# LINK.net
KiCad netlist of a schematic drawn in Altium Designer
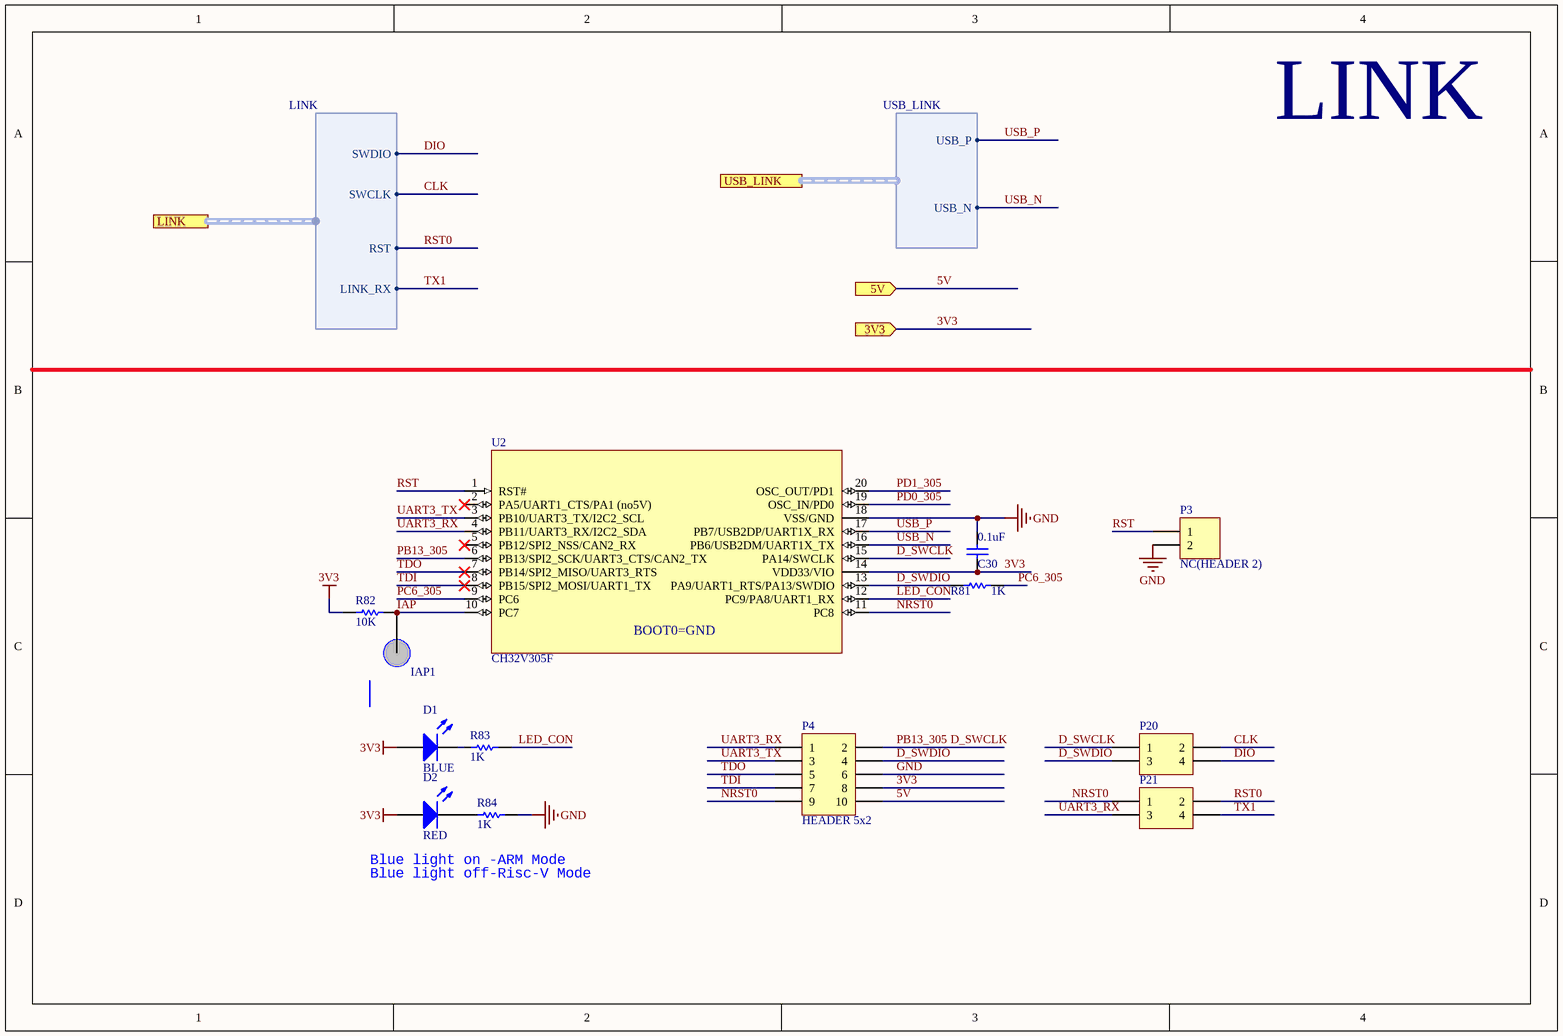
[diagram p0: LINK.SchDoc]

(export (version "E")
  (design (tool "Eeschema 10.0.6"))
  (components
    (comp (ref "C30")
      (value "0.1uF")
      (footprint "0402_C")
      (description "Capacitor")
      (libsource (lib "Miscellaneous Devices") (part "Cap"))
    )
    (comp (ref "D1")
      (value "BLUE")
      (footprint "0603+")
      (description "Typical RED, GREEN, YELLOW, AMBER GaAs LED")
      (fields (field (name "PUBLISHER") "Altium Limited"))
      (libsource (lib "MYLIB") (part "D0603"))
    )
    (comp (ref "D2")
      (value "RED")
      (footprint "0603+")
      (description "Typical RED, GREEN, YELLOW, AMBER GaAs LED")
      (fields (field (name "PUBLISHER") "Altium Limited"))
      (libsource (lib "MYLIB") (part "D0603"))
    )
    (comp (ref "IAP1")
      (value "Testpoint")
      (footprint "TESTPOINT1")
      (description "测试点")
      (libsource (lib "wch_sch_others") (part "Testpoint"))
    )
    (comp (ref "P3")
      (value "NC(HEADER 2)")
      (footprint "MYPCB:SIP2-2.54mm")
      (description "Header, 2-Pin")
      (libsource (lib "wch_sch_others") (part "HEADER 2"))
    )
    (comp (ref "P4")
      (value "HEADER 5x2")
      (footprint "MYPCB:IDC10-2.54mm")
      (description "Header, 5-Pin, Dual row")
      (libsource (lib "wch_sch_others") (part "HEADER 5x2"))
    )
    (comp (ref "P20")
      (value "HEADER 2x2")
      (footprint "MYPCB:IDC4-2.54MM")
      (description "Header, 2-Pin, Dual row")
      (libsource (lib "wch_sch_others") (part "HEADER 2x2"))
    )
    (comp (ref "P21")
      (value "HEADER 2x2")
      (footprint "MYPCB:IDC4-2.54MM")
      (description "Header, 2-Pin, Dual row")
      (libsource (lib "wch_sch_others") (part "HEADER 2x2"))
    )
    (comp (ref "R81")
      (value "1K")
      (footprint "0402")
      (description "Resistor")
      (fields (field (name "PUBLISHER") "Altium Limited"))
      (libsource (lib "MYLIB") (part "0603-1"))
    )
    (comp (ref "R82")
      (value "10K")
      (footprint "0402")
      (description "Resistor")
      (fields (field (name "PUBLISHER") "Altium Limited"))
      (libsource (lib "MYLIB") (part "0603-1"))
    )
    (comp (ref "R83")
      (value "1K")
      (footprint "0402")
      (description "Resistor")
      (fields (field (name "PUBLISHER") "Altium Limited"))
      (libsource (lib "MYLIB") (part "0603-1"))
    )
    (comp (ref "R84")
      (value "1K")
      (footprint "0402")
      (description "Resistor")
      (fields (field (name "PUBLISHER") "Altium Limited"))
      (libsource (lib "MYLIB") (part "0603-1"))
    )
    (comp (ref "U2")
      (value "CH32V305F")
      (footprint "TSSOP20")
      (description "RISC-V FPU HD-MCU, 144MHz, USB_480M, CAN, UART*2, SPI")
      (libsource (lib "CHXXX") (part "CH32V305F"))
    )
  )
  (nets
    (net (code "3") (name "/5V") (class "Default")
      (node (ref "P4") (pin "10") (pinfunction "10_10") (pintype "passive"))
    )
    (net (code "4") (name "/CLK") (class "Default")
      (node (ref "P20") (pin "2") (pinfunction "2_2") (pintype "passive"))
    )
    (net (code "5") (name "/DIO") (class "Default")
      (node (ref "P20") (pin "4") (pinfunction "4_4") (pintype "passive"))
    )
    (net (code "6") (name "/D_SWCLK") (class "Default")
      (node (ref "P20") (pin "1") (pinfunction "1_1") (pintype "passive"))
      (node (ref "P4") (pin "2") (pinfunction "2_2") (pintype "passive"))
      (node (ref "U2") (pin "15") (pinfunction "PA14/SWCLK_15") (pintype "bidirectional"))
      (node (ref "U2") (pin "6") (pinfunction "PB13/SPI2_SCK/UART3_CTS/CAN2_TX_6") (pintype "bidirectional"))
    )
    (net (code "7") (name "/D_SWDIO") (class "Default")
      (node (ref "P20") (pin "3") (pinfunction "3_3") (pintype "passive"))
      (node (ref "P4") (pin "4") (pinfunction "4_4") (pintype "passive"))
      (node (ref "R81") (pin "1") (pinfunction "1_1") (pintype "passive"))
      (node (ref "U2") (pin "13") (pinfunction "PA9/UART1_RTS/PA13/SWDIO_13") (pintype "bidirectional"))
    )
    (net (code "8") (name "/IAP") (class "Default")
      (node (ref "IAP1") (pin "1") (pinfunction "point_1") (pintype "passive"))
      (node (ref "R82") (pin "1") (pinfunction "1_1") (pintype "passive"))
      (node (ref "U2") (pin "10") (pinfunction "PC7_10") (pintype "bidirectional"))
    )
    (net (code "9") (name "/LED_CON") (class "Default")
      (node (ref "R83") (pin "1") (pinfunction "1_1") (pintype "passive"))
      (node (ref "U2") (pin "12") (pinfunction "PC9/PA8/UART1_RX_12") (pintype "bidirectional"))
    )
    (net (code "10") (name "/NRST0") (class "Default")
      (node (ref "P21") (pin "1") (pinfunction "1_1") (pintype "passive"))
      (node (ref "P4") (pin "9") (pinfunction "9_9") (pintype "passive"))
      (node (ref "U2") (pin "11") (pinfunction "PC8_11") (pintype "bidirectional"))
    )
    (net (code "11") (name "/PC6_305") (class "Default")
      (node (ref "R81") (pin "2") (pinfunction "2_2") (pintype "passive"))
      (node (ref "U2") (pin "9") (pinfunction "PC6_9") (pintype "bidirectional"))
    )
    (net (code "12") (name "/PD0_305") (class "Default")
      (node (ref "U2") (pin "19") (pinfunction "OSC_IN/PD0_19") (pintype "bidirectional"))
    )
    (net (code "13") (name "/PD1_305") (class "Default")
      (node (ref "U2") (pin "20") (pinfunction "OSC_OUT/PD1_20") (pintype "bidirectional"))
    )
    (net (code "14") (name "/RST") (class "Default")
      (node (ref "P3") (pin "1") (pinfunction "1_1") (pintype "passive"))
      (node (ref "U2") (pin "1") (pinfunction "RST#_1") (pintype "input"))
    )
    (net (code "15") (name "/RST0") (class "Default")
      (node (ref "P21") (pin "2") (pinfunction "2_2") (pintype "passive"))
    )
    (net (code "16") (name "/TDI") (class "Default")
      (node (ref "P4") (pin "7") (pinfunction "7_7") (pintype "passive"))
      (node (ref "U2") (pin "8") (pinfunction "PB15/SPI2_MOSI/UART1_TX_8") (pintype "bidirectional"))
    )
    (net (code "17") (name "/TDO") (class "Default")
      (node (ref "P4") (pin "5") (pinfunction "5_5") (pintype "passive"))
      (node (ref "U2") (pin "7") (pinfunction "PB14/SPI2_MISO/UART3_RTS_7") (pintype "bidirectional"))
    )
    (net (code "18") (name "/TX1") (class "Default")
      (node (ref "P21") (pin "4") (pinfunction "4_4") (pintype "passive"))
    )
    (net (code "19") (name "/UART3_RX") (class "Default")
      (node (ref "P21") (pin "3") (pinfunction "3_3") (pintype "passive"))
      (node (ref "P4") (pin "1") (pinfunction "1_1") (pintype "passive"))
      (node (ref "U2") (pin "4") (pinfunction "PB11/UART3_RX/I2C2_SDA_4") (pintype "bidirectional"))
    )
    (net (code "20") (name "/UART3_TX") (class "Default")
      (node (ref "P4") (pin "3") (pinfunction "3_3") (pintype "passive"))
      (node (ref "U2") (pin "3") (pinfunction "PB10/UART3_TX/I2C2_SCL_3") (pintype "bidirectional"))
    )
    (net (code "21") (name "/USB_N") (class "Default")
      (node (ref "U2") (pin "16") (pinfunction "PB6/USB2DM/UART1X_TX_16") (pintype "bidirectional"))
    )
    (net (code "22") (name "/USB_P") (class "Default")
      (node (ref "U2") (pin "17") (pinfunction "PB7/USB2DP/UART1X_RX_17") (pintype "bidirectional"))
    )
    (net (code "25") (name "3V3") (class "Default")
      (node (ref "C30") (pin "1") (pinfunction "1_1") (pintype "passive"))
      (node (ref "D1") (pin "1") (pinfunction "A_1") (pintype "passive"))
      (node (ref "D2") (pin "1") (pinfunction "A_1") (pintype "passive"))
      (node (ref "P4") (pin "8") (pinfunction "8_8") (pintype "passive"))
      (node (ref "R82") (pin "2") (pinfunction "2_2") (pintype "passive"))
      (node (ref "U2") (pin "14") (pinfunction "VDD33/VIO_14") (pintype "power_in"))
    )
    (net (code "26") (name "GND") (class "Default")
      (node (ref "C30") (pin "2") (pinfunction "2_2") (pintype "passive"))
      (node (ref "P3") (pin "2") (pinfunction "2_2") (pintype "passive"))
      (node (ref "P4") (pin "6") (pinfunction "6_6") (pintype "passive"))
      (node (ref "R84") (pin "1") (pinfunction "1_1") (pintype "passive"))
      (node (ref "U2") (pin "18") (pinfunction "VSS/GND_18") (pintype "power_in"))
    )
    (net (code "27") (name "Net-(D1-K)") (class "Default")
      (node (ref "D1") (pin "2") (pinfunction "K_2") (pintype "passive"))
      (node (ref "R83") (pin "2") (pinfunction "2_2") (pintype "passive"))
    )
    (net (code "28") (name "Net-(D2-K)") (class "Default")
      (node (ref "D2") (pin "2") (pinfunction "K_2") (pintype "passive"))
      (node (ref "R84") (pin "2") (pinfunction "2_2") (pintype "passive"))
    )
    (net (code "29") (name "unconnected-(U2-PA5{slash}UART1_CTS{slash}PA1_(no5V)-Pad2)") (class "Default")
      (node (ref "U2") (pin "2") (pinfunction "PA5/UART1_CTS/PA1_(no5V)_2") (pintype "bidirectional+no_connect"))
    )
    (net (code "30") (name "unconnected-(U2-PB12{slash}SPI2_NSS{slash}CAN2_RX-Pad5)") (class "Default")
      (node (ref "U2") (pin "5") (pinfunction "PB12/SPI2_NSS/CAN2_RX_5") (pintype "bidirectional+no_connect"))
    )
  )
)
